# ESPNTPServer.net
KiCad netlist of a schematic drawn in EAGLE
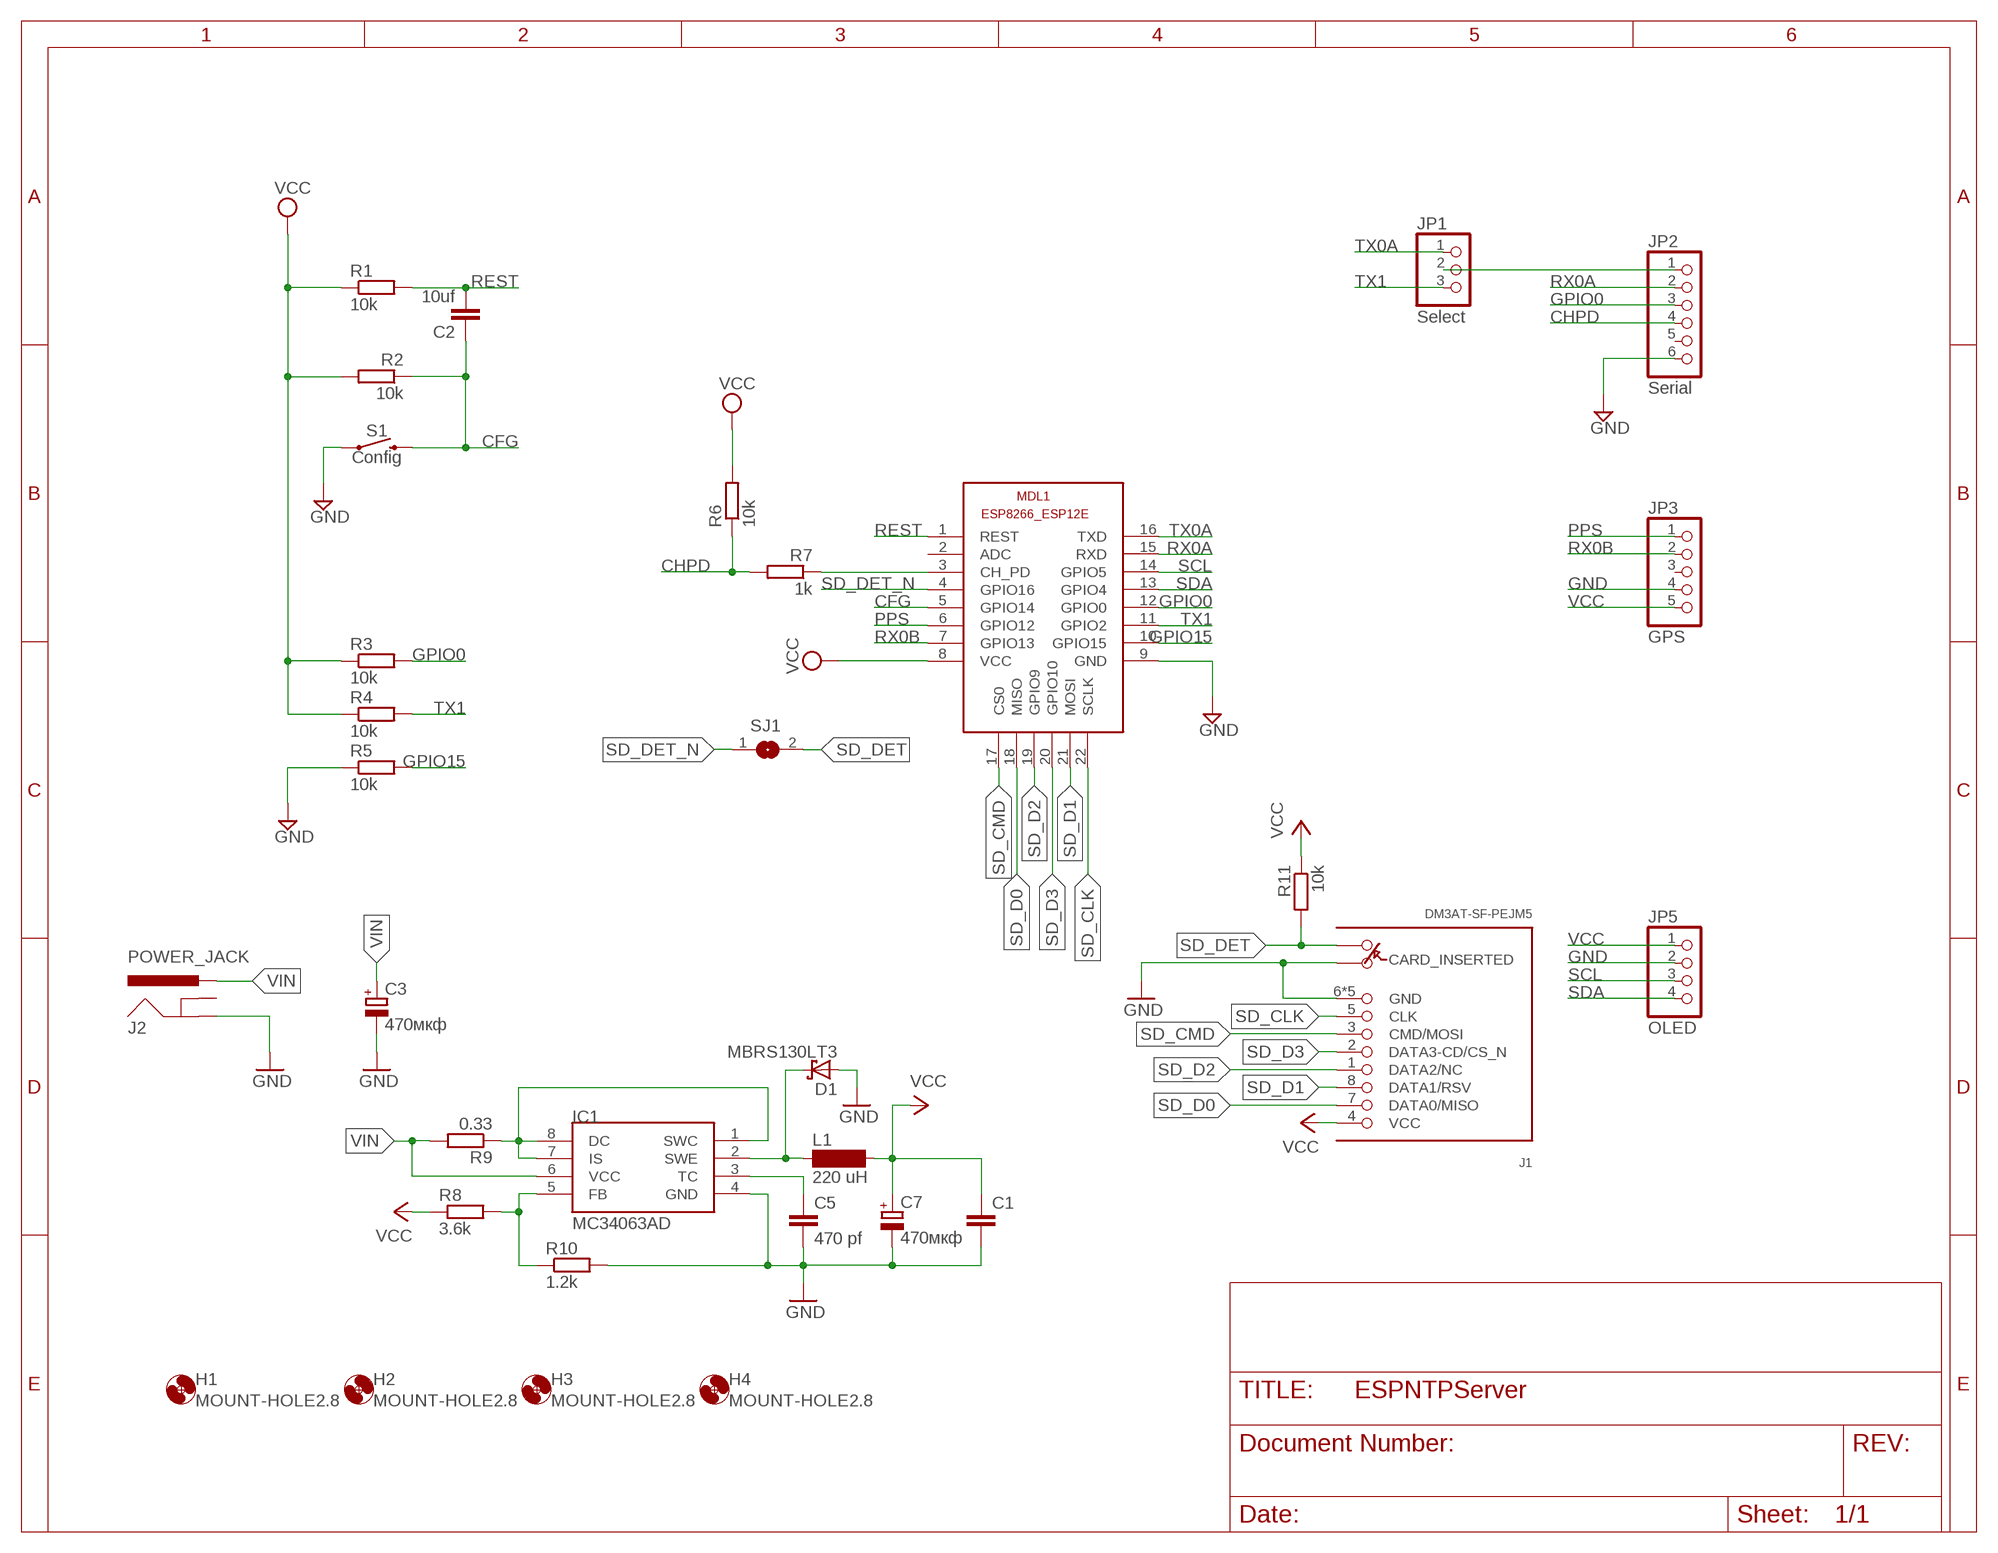
[diagram p0: schematic, sheet 1]

(export (version "E")
  (design (tool "Eeschema 10.0.6"))
  (components
    (comp (ref "C1")
      (value "C-EUC1206")
      (footprint "eagle-import:C1206")
      (libsource (lib "eagle-import") (part "resistor_C-EUC1206"))
    )
    (comp (ref "C2")
      (value "10uf")
      (footprint "eagle-import:C050-025X075")
      (libsource (lib "eagle-import") (part "C-EU050-025X075"))
    )
    (comp (ref "C3")
      (value "470мкф")
      (footprint "eagle-import:E3,5-8")
      (libsource (lib "eagle-import") (part "CPOL-EUE3.5-8"))
    )
    (comp (ref "C5")
      (value "470 pf")
      (footprint "eagle-import:C1206")
      (libsource (lib "eagle-import") (part "resistor_C-EUC1206"))
    )
    (comp (ref "C7")
      (value "470мкф")
      (footprint "eagle-import:E3,5-8")
      (libsource (lib "eagle-import") (part "CPOL-EUE3.5-8"))
    )
    (comp (ref "D1")
      (value "MBRS130LT3")
      (footprint "eagle-import:SMB")
      (libsource (lib "eagle-import") (part "MBRS130LT3"))
    )
    (comp (ref "H1")
      (value "MOUNT-HOLE2.8")
      (footprint "eagle-import:2,8")
      (libsource (lib "eagle-import") (part "MOUNT-HOLE2.8"))
    )
    (comp (ref "H2")
      (value "MOUNT-HOLE2.8")
      (footprint "eagle-import:2,8")
      (libsource (lib "eagle-import") (part "MOUNT-HOLE2.8"))
    )
    (comp (ref "H3")
      (value "MOUNT-HOLE2.8")
      (footprint "eagle-import:2,8")
      (libsource (lib "eagle-import") (part "MOUNT-HOLE2.8"))
    )
    (comp (ref "H4")
      (value "MOUNT-HOLE2.8")
      (footprint "eagle-import:2,8")
      (libsource (lib "eagle-import") (part "MOUNT-HOLE2.8"))
    )
    (comp (ref "IC1")
      (value "MC34063AD")
      (footprint "eagle-import:SOIC8")
      (libsource (lib "eagle-import") (part "MC34063AD"))
    )
    (comp (ref "J1")
      (value "DM3AT-SF-PEJM5")
      (footprint "eagle-import:DM3AT-SF-PEJM5")
      (fields (field (name "MANUFACTURER") "Hirose Electric Co Ltd"))
      (libsource (lib "eagle-import") (part "DM3AT-SF-PEJM5"))
    )
    (comp (ref "J2")
      (value "POWER_JACK")
      (footprint "eagle-import:POWER_JACK_PTH")
      (libsource (lib "eagle-import") (part "POWER_JACK"))
    )
    (comp (ref "JP1")
      (value "Select")
      (footprint "eagle-import:1X03")
      (libsource (lib "eagle-import") (part "PINHD-1X3"))
    )
    (comp (ref "JP2")
      (value "Serial")
      (footprint "eagle-import:1X06")
      (libsource (lib "eagle-import") (part "PINHD-1X6"))
    )
    (comp (ref "JP3")
      (value "GPS")
      (footprint "eagle-import:1X05")
      (libsource (lib "eagle-import") (part "PINHD-1X5"))
    )
    (comp (ref "JP5")
      (value "OLED")
      (footprint "eagle-import:1X04")
      (libsource (lib "eagle-import") (part "PINHD-1X4"))
    )
    (comp (ref "L1")
      (value "220 uH")
      (footprint "eagle-import:SD12K-82")
      (libsource (lib "eagle-import") (part "SD12K-82"))
    )
    (comp (ref "MDL1")
      (value "ESP8266-12F")
      (footprint "eagle-import:ESP8266-ESP12E")
      (libsource (lib "eagle-import") (part "ESP8266-12EESP8266-ESP12E"))
    )
    (comp (ref "R1")
      (value "10k")
      (footprint "eagle-import:M1206")
      (libsource (lib "eagle-import") (part "R-EU_M1206"))
    )
    (comp (ref "R2")
      (value "10k")
      (footprint "eagle-import:M1206")
      (libsource (lib "eagle-import") (part "R-EU_M1206"))
    )
    (comp (ref "R3")
      (value "10k")
      (footprint "eagle-import:M1206")
      (libsource (lib "eagle-import") (part "R-EU_M1206"))
    )
    (comp (ref "R4")
      (value "10k")
      (footprint "eagle-import:M1206")
      (libsource (lib "eagle-import") (part "R-EU_M1206"))
    )
    (comp (ref "R5")
      (value "10k")
      (footprint "eagle-import:M1206")
      (libsource (lib "eagle-import") (part "R-EU_M1206"))
    )
    (comp (ref "R6")
      (value "10k")
      (footprint "eagle-import:M1206")
      (libsource (lib "eagle-import") (part "R-EU_M1206"))
    )
    (comp (ref "R7")
      (value "1k")
      (footprint "eagle-import:M1206")
      (libsource (lib "eagle-import") (part "R-EU_M1206"))
    )
    (comp (ref "R8")
      (value "3.6k")
      (footprint "eagle-import:M1206")
      (libsource (lib "eagle-import") (part "R-EU_M1206"))
    )
    (comp (ref "R9")
      (value "0.33")
      (footprint "eagle-import:0411V")
      (libsource (lib "eagle-import") (part "R-EU_0411/3V"))
    )
    (comp (ref "R10")
      (value "1.2k")
      (footprint "eagle-import:M1206")
      (libsource (lib "eagle-import") (part "R-EU_M1206"))
    )
    (comp (ref "R11")
      (value "10k")
      (footprint "eagle-import:M1206")
      (libsource (lib "eagle-import") (part "R-EU_M1206"))
    )
    (comp (ref "S1")
      (value "Config")
      (footprint "eagle-import:TACTILE_SWITCH_PTH_6.0MM")
      (libsource (lib "eagle-import") (part "MOMENTARY-SWITCH-SPST-PTH-6.0MM"))
    )
    (comp (ref "SJ1") (value "SJ") (footprint "eagle-import:SJ") (libsource (lib "eagle-import") (part "SJ")))
  )
  (nets
    (net (code "1") (name "/CFG") (class "Default")
      (node (ref "C2") (pin "1") (pinfunction "1_1") (pintype "passive"))
      (node (ref "MDL1") (pin "5") (pinfunction "GPIO14_5") (pintype "bidirectional"))
      (node (ref "R2") (pin "1") (pinfunction "1_1") (pintype "passive"))
      (node (ref "S1") (pin "3") (pinfunction "2_3") (pintype "passive"))
    )
    (net (code "2") (name "/CHPD") (class "Default")
      (node (ref "JP2") (pin "4") (pinfunction "4_4") (pintype "passive"))
      (node (ref "R6") (pin "1") (pinfunction "1_1") (pintype "passive"))
      (node (ref "R7") (pin "2") (pinfunction "2_2") (pintype "passive"))
    )
    (net (code "3") (name "/GPIO0") (class "Default")
      (node (ref "JP2") (pin "3") (pinfunction "3_3") (pintype "passive"))
      (node (ref "MDL1") (pin "12") (pinfunction "GPIO0_12") (pintype "bidirectional"))
      (node (ref "R3") (pin "2") (pinfunction "2_2") (pintype "passive"))
    )
    (net (code "4") (name "/GPIO15") (class "Default")
      (node (ref "MDL1") (pin "10") (pinfunction "GPIO15_10") (pintype "bidirectional"))
      (node (ref "R5") (pin "2") (pinfunction "2_2") (pintype "passive"))
    )
    (net (code "5") (name "/PPS") (class "Default")
      (node (ref "JP3") (pin "1") (pinfunction "1_1") (pintype "passive"))
      (node (ref "MDL1") (pin "6") (pinfunction "GPIO12_6") (pintype "bidirectional"))
    )
    (net (code "6") (name "/REST") (class "Default")
      (node (ref "C2") (pin "2") (pinfunction "2_2") (pintype "passive"))
      (node (ref "MDL1") (pin "1") (pinfunction "REST_1") (pintype "bidirectional"))
      (node (ref "R1") (pin "2") (pinfunction "2_2") (pintype "passive"))
    )
    (net (code "7") (name "/RX0A") (class "Default")
      (node (ref "JP2") (pin "2") (pinfunction "2_2") (pintype "passive"))
      (node (ref "MDL1") (pin "15") (pinfunction "RXD_15") (pintype "bidirectional"))
    )
    (net (code "8") (name "/RX0B") (class "Default")
      (node (ref "JP3") (pin "2") (pinfunction "2_2") (pintype "passive"))
      (node (ref "MDL1") (pin "7") (pinfunction "GPIO13_7") (pintype "bidirectional"))
    )
    (net (code "9") (name "/SCL") (class "Default")
      (node (ref "JP5") (pin "3") (pinfunction "3_3") (pintype "passive"))
      (node (ref "MDL1") (pin "14") (pinfunction "GPIO5_14") (pintype "bidirectional"))
    )
    (net (code "10") (name "/SDA") (class "Default")
      (node (ref "JP5") (pin "4") (pinfunction "4_4") (pintype "passive"))
      (node (ref "MDL1") (pin "13") (pinfunction "GPIO4_13") (pintype "bidirectional"))
    )
    (net (code "11") (name "/TX0A") (class "Default")
      (node (ref "JP1") (pin "1") (pinfunction "1_1") (pintype "passive"))
      (node (ref "MDL1") (pin "16") (pinfunction "TXD_16") (pintype "bidirectional"))
    )
    (net (code "12") (name "/TX1") (class "Default")
      (node (ref "JP1") (pin "3") (pinfunction "3_3") (pintype "passive"))
      (node (ref "MDL1") (pin "11") (pinfunction "GPIO2_11") (pintype "bidirectional"))
      (node (ref "R4") (pin "2") (pinfunction "2_2") (pintype "passive"))
    )
    (net (code "13") (name "GND") (class "Default")
      (node (ref "C1") (pin "2") (pinfunction "2_2") (pintype "passive"))
      (node (ref "C3") (pin "-") (pinfunction "-_-") (pintype "passive"))
      (node (ref "C5") (pin "2") (pinfunction "2_2") (pintype "passive"))
      (node (ref "C7") (pin "-") (pinfunction "-_-") (pintype "passive"))
      (node (ref "D1") (pin "A") (pinfunction "A_A") (pintype "passive"))
      (node (ref "IC1") (pin "4") (pinfunction "GND_4") (pintype "passive"))
      (node (ref "J1") (pin "6") (pinfunction "GND_6") (pintype "bidirectional"))
      (node (ref "J1") (pin "A") (pinfunction "A_A") (pintype "bidirectional"))
      (node (ref "J1") (pin "MOUNT0") (pinfunction "GND_MOUNT0") (pintype "bidirectional"))
      (node (ref "J1") (pin "MOUNT1") (pinfunction "GND_MOUNT1") (pintype "bidirectional"))
      (node (ref "J1") (pin "MOUNT2") (pinfunction "GND_MOUNT2") (pintype "bidirectional"))
      (node (ref "J1") (pin "MOUNT3") (pinfunction "GND_MOUNT3") (pintype "bidirectional"))
      (node (ref "J2") (pin "GND") (pinfunction "GND_GND") (pintype "bidirectional"))
      (node (ref "JP2") (pin "6") (pinfunction "6_6") (pintype "passive"))
      (node (ref "JP3") (pin "4") (pinfunction "4_4") (pintype "passive"))
      (node (ref "JP5") (pin "2") (pinfunction "2_2") (pintype "passive"))
      (node (ref "MDL1") (pin "9") (pinfunction "GND_9") (pintype "bidirectional"))
      (node (ref "R10") (pin "2") (pinfunction "2_2") (pintype "passive"))
      (node (ref "R5") (pin "1") (pinfunction "1_1") (pintype "passive"))
      (node (ref "S1") (pin "1") (pinfunction "1_1") (pintype "passive"))
    )
    (net (code "14") (name "Net-(IC1-DC)") (class "Default")
      (node (ref "IC1") (pin "1") (pinfunction "SWC_1") (pintype "passive"))
      (node (ref "IC1") (pin "7") (pinfunction "IS_7") (pintype "passive"))
      (node (ref "IC1") (pin "8") (pinfunction "DC_8") (pintype "passive"))
      (node (ref "R9") (pin "1") (pinfunction "1_1") (pintype "passive"))
    )
    (net (code "15") (name "Net-(IC1-FB)") (class "Default")
      (node (ref "IC1") (pin "5") (pinfunction "FB_5") (pintype "passive"))
      (node (ref "R10") (pin "1") (pinfunction "1_1") (pintype "passive"))
      (node (ref "R8") (pin "2") (pinfunction "2_2") (pintype "passive"))
    )
    (net (code "16") (name "Net-(IC1-SWE)") (class "Default")
      (node (ref "D1") (pin "C") (pinfunction "C_C") (pintype "passive"))
      (node (ref "IC1") (pin "2") (pinfunction "SWE_2") (pintype "passive"))
      (node (ref "L1") (pin "1") (pinfunction "1_1") (pintype "passive"))
    )
    (net (code "17") (name "Net-(IC1-TC)") (class "Default")
      (node (ref "C5") (pin "1") (pinfunction "1_1") (pintype "passive"))
      (node (ref "IC1") (pin "3") (pinfunction "TC_3") (pintype "passive"))
    )
    (net (code "18") (name "Net-(JP1-Pad2)") (class "Default")
      (node (ref "JP1") (pin "2") (pinfunction "2_2") (pintype "passive"))
      (node (ref "JP2") (pin "1") (pinfunction "1_1") (pintype "passive"))
    )
    (net (code "19") (name "Net-(MDL1-CH_PD)") (class "Default")
      (node (ref "MDL1") (pin "3") (pinfunction "CH_PD_3") (pintype "bidirectional"))
      (node (ref "R7") (pin "1") (pinfunction "1_1") (pintype "passive"))
    )
    (net (code "20") (name "SD_CLK") (class "Default")
      (node (ref "J1") (pin "5") (pinfunction "CLK_5") (pintype "bidirectional"))
      (node (ref "MDL1") (pin "22") (pinfunction "SCLK_22") (pintype "bidirectional"))
    )
    (net (code "21") (name "SD_CMD") (class "Default")
      (node (ref "J1") (pin "3") (pinfunction "CMD/MOSI_3") (pintype "bidirectional"))
      (node (ref "MDL1") (pin "17") (pinfunction "CS0_17") (pintype "bidirectional"))
    )
    (net (code "22") (name "SD_D0") (class "Default")
      (node (ref "J1") (pin "7") (pinfunction "DATA0/MISO_7") (pintype "bidirectional"))
      (node (ref "MDL1") (pin "18") (pinfunction "MISO_18") (pintype "bidirectional"))
    )
    (net (code "23") (name "SD_D1") (class "Default")
      (node (ref "J1") (pin "8") (pinfunction "DATA1/RSV_8") (pintype "bidirectional"))
      (node (ref "MDL1") (pin "21") (pinfunction "MOSI_21") (pintype "bidirectional"))
    )
    (net (code "24") (name "SD_D2") (class "Default")
      (node (ref "J1") (pin "1") (pinfunction "DATA2/NC_1") (pintype "bidirectional"))
      (node (ref "MDL1") (pin "19") (pinfunction "GPIO9_19") (pintype "bidirectional"))
    )
    (net (code "25") (name "SD_D3") (class "Default")
      (node (ref "J1") (pin "2") (pinfunction "DATA3-CD/CS_N_2") (pintype "bidirectional"))
      (node (ref "MDL1") (pin "20") (pinfunction "GPIO10_20") (pintype "bidirectional"))
    )
    (net (code "26") (name "SD_DET") (class "Default")
      (node (ref "J1") (pin "B") (pinfunction "B_B") (pintype "bidirectional"))
      (node (ref "R11") (pin "2") (pinfunction "2_2") (pintype "passive"))
      (node (ref "SJ1") (pin "2") (pinfunction "2_2") (pintype "passive"))
    )
    (net (code "27") (name "SD_DET_N") (class "Default")
      (node (ref "MDL1") (pin "4") (pinfunction "GPIO16_4") (pintype "bidirectional"))
      (node (ref "SJ1") (pin "1") (pinfunction "1_1") (pintype "passive"))
    )
    (net (code "28") (name "VCC") (class "Default")
      (node (ref "C1") (pin "1") (pinfunction "1_1") (pintype "passive"))
      (node (ref "C7") (pin "+") (pinfunction "+_+") (pintype "passive"))
      (node (ref "J1") (pin "4") (pinfunction "VCC_4") (pintype "bidirectional"))
      (node (ref "JP3") (pin "5") (pinfunction "5_5") (pintype "passive"))
      (node (ref "JP5") (pin "1") (pinfunction "1_1") (pintype "passive"))
      (node (ref "L1") (pin "2") (pinfunction "2_2") (pintype "passive"))
      (node (ref "MDL1") (pin "8") (pinfunction "VCC_8") (pintype "bidirectional"))
      (node (ref "R1") (pin "1") (pinfunction "1_1") (pintype "passive"))
      (node (ref "R11") (pin "1") (pinfunction "1_1") (pintype "passive"))
      (node (ref "R2") (pin "2") (pinfunction "2_2") (pintype "passive"))
      (node (ref "R3") (pin "1") (pinfunction "1_1") (pintype "passive"))
      (node (ref "R4") (pin "1") (pinfunction "1_1") (pintype "passive"))
      (node (ref "R6") (pin "2") (pinfunction "2_2") (pintype "passive"))
      (node (ref "R8") (pin "1") (pinfunction "1_1") (pintype "passive"))
    )
    (net (code "29") (name "VIN") (class "Default")
      (node (ref "C3") (pin "+") (pinfunction "+_+") (pintype "passive"))
      (node (ref "IC1") (pin "6") (pinfunction "VCC_6") (pintype "passive"))
      (node (ref "J2") (pin "PWR") (pinfunction "PWR_PWR") (pintype "bidirectional"))
      (node (ref "R9") (pin "2") (pinfunction "2_2") (pintype "passive"))
    )
    (net (code "30") (name "unconnected-(J2-PadGNDBREAK)") (class "Default")
      (node (ref "J2") (pin "GNDBREAK") (pinfunction "GNDBREAK_GNDBREAK") (pintype "bidirectional"))
    )
    (net (code "31") (name "unconnected-(JP2-Pad5)") (class "Default")
      (node (ref "JP2") (pin "5") (pinfunction "5_5") (pintype "passive"))
    )
    (net (code "32") (name "unconnected-(JP3-Pad3)") (class "Default")
      (node (ref "JP3") (pin "3") (pinfunction "3_3") (pintype "passive"))
    )
    (net (code "33") (name "unconnected-(MDL1-ADC-Pad2)") (class "Default")
      (node (ref "MDL1") (pin "2") (pinfunction "ADC_2") (pintype "bidirectional"))
    )
  )
)
